# Servorino_FT230X_brick_logic.net
KiCad netlist of a schematic drawn in EAGLE
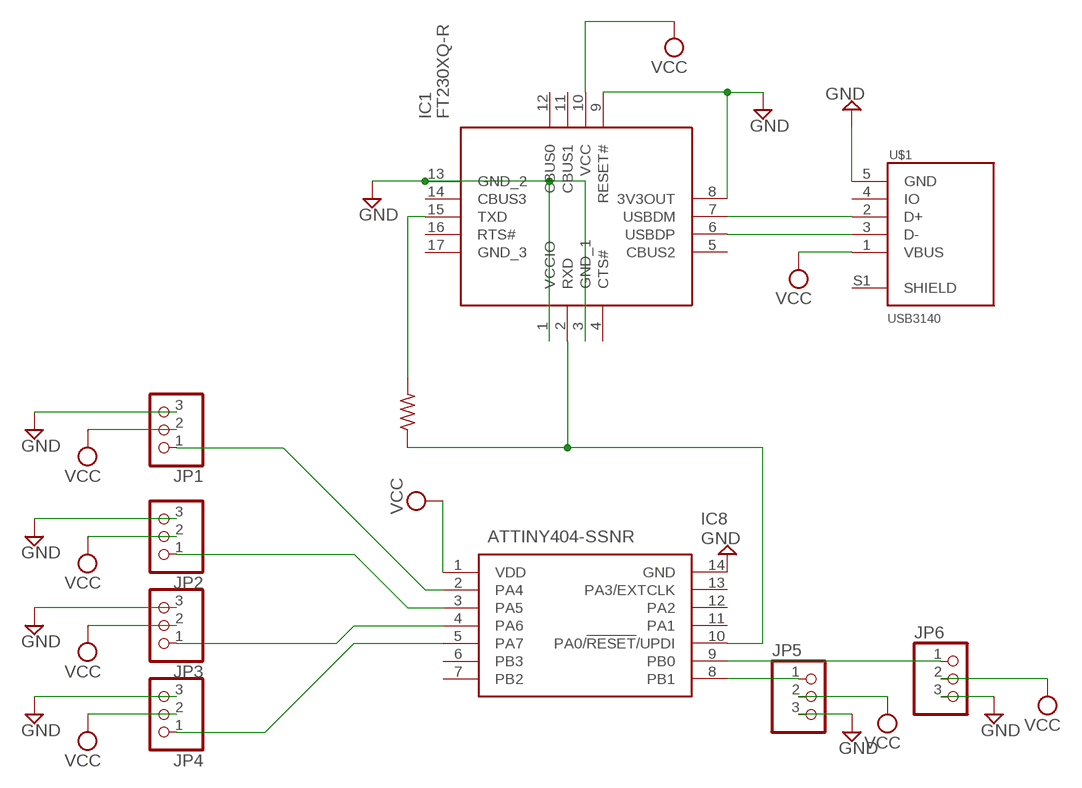
[diagram p0: schematic, sheet 1]

(export (version "E")
  (design (tool "Eeschema 10.0.6"))
  (components
    (comp (ref "IC1")
      (value "FT230XQ-R")
      (footprint "eagle-import:QFN65P400X400X80-17N")
      (fields (field (name "MOUSER_PART_NUMBER") "895-FT230XQ-R"))
      (libsource (lib "eagle-import") (part "FT230XQ-R"))
    )
    (comp (ref "IC8")
      (value "ATTINY404-SSNR")
      (footprint "eagle-import:SOIC127P600X175-14N")
      (fields (field (name "MOUSER_PART_NUMBER") "556-ATTINY404-SSNR"))
      (libsource (lib "eagle-import") (part "ATTINY404-SSNR"))
    )
    (comp (ref "JP1")
      (value "PINHD-1X3")
      (footprint "eagle-import:1X03")
      (libsource (lib "eagle-import") (part "PINHD-1X3"))
    )
    (comp (ref "JP2")
      (value "PINHD-1X3")
      (footprint "eagle-import:1X03")
      (libsource (lib "eagle-import") (part "PINHD-1X3"))
    )
    (comp (ref "JP3")
      (value "PINHD-1X3")
      (footprint "eagle-import:1X03")
      (libsource (lib "eagle-import") (part "PINHD-1X3"))
    )
    (comp (ref "JP4")
      (value "PINHD-1X3")
      (footprint "eagle-import:1X03")
      (libsource (lib "eagle-import") (part "PINHD-1X3"))
    )
    (comp (ref "JP5")
      (value "PINHD-1X3")
      (footprint "eagle-import:1X03")
      (libsource (lib "eagle-import") (part "PINHD-1X3"))
    )
    (comp (ref "JP6")
      (value "PINHD-1X3")
      (footprint "eagle-import:1X03")
      (libsource (lib "eagle-import") (part "PINHD-1X3"))
    )
    (comp (ref "R6")
      (value "470")
      (footprint "eagle-import:R0805")
      (libsource (lib "eagle-import") (part "R-US_R0805"))
    )
    (comp (ref "U$1")
      (value "USB3140")
      (footprint "eagle-import:USB3140-30-0170-0-C")
      (libsource (lib "eagle-import") (part "USB3140"))
    )
  )
  (nets
    (net (code "1") (name "GND") (class "Default")
      (node (ref "IC1") (pin "1") (pinfunction "VCCIO_1") (pintype "bidirectional"))
      (node (ref "IC1") (pin "13") (pinfunction "GND_2_13") (pintype "bidirectional"))
      (node (ref "IC1") (pin "3") (pinfunction "GND_1_3") (pintype "bidirectional"))
      (node (ref "IC1") (pin "8") (pinfunction "3V3OUT_8") (pintype "bidirectional"))
      (node (ref "IC1") (pin "9") (pinfunction "RESET#_9") (pintype "bidirectional"))
      (node (ref "IC8") (pin "14") (pinfunction "GND_14") (pintype "bidirectional"))
      (node (ref "JP1") (pin "3") (pinfunction "3_3") (pintype "passive"))
      (node (ref "JP2") (pin "3") (pinfunction "3_3") (pintype "passive"))
      (node (ref "JP3") (pin "3") (pinfunction "3_3") (pintype "passive"))
      (node (ref "JP4") (pin "3") (pinfunction "3_3") (pintype "passive"))
      (node (ref "JP5") (pin "3") (pinfunction "3_3") (pintype "passive"))
      (node (ref "JP6") (pin "3") (pinfunction "3_3") (pintype "passive"))
      (node (ref "U$1") (pin "5") (pinfunction "GND_5") (pintype "passive"))
    )
    (net (code "2") (name "Net-(IC1-RXD)") (class "Default")
      (node (ref "IC1") (pin "2") (pinfunction "RXD_2") (pintype "bidirectional"))
      (node (ref "IC8") (pin "10") (pinfunction "PA0/~{RESET}/UPDI_10") (pintype "bidirectional"))
      (node (ref "R6") (pin "1") (pinfunction "1_1") (pintype "passive"))
    )
    (net (code "3") (name "Net-(IC1-TXD)") (class "Default")
      (node (ref "IC1") (pin "15") (pinfunction "TXD_15") (pintype "bidirectional"))
      (node (ref "R6") (pin "2") (pinfunction "2_2") (pintype "passive"))
    )
    (net (code "4") (name "Net-(IC1-USBDM)") (class "Default")
      (node (ref "IC1") (pin "7") (pinfunction "USBDM_7") (pintype "bidirectional"))
      (node (ref "U$1") (pin "2") (pinfunction "D+_2") (pintype "passive"))
    )
    (net (code "5") (name "Net-(IC1-USBDP)") (class "Default")
      (node (ref "IC1") (pin "6") (pinfunction "USBDP_6") (pintype "bidirectional"))
      (node (ref "U$1") (pin "3") (pinfunction "D-_3") (pintype "passive"))
    )
    (net (code "6") (name "Net-(IC8-PA4)") (class "Default")
      (node (ref "IC8") (pin "2") (pinfunction "PA4_2") (pintype "bidirectional"))
      (node (ref "JP1") (pin "1") (pinfunction "1_1") (pintype "passive"))
    )
    (net (code "7") (name "Net-(IC8-PA5)") (class "Default")
      (node (ref "IC8") (pin "3") (pinfunction "PA5_3") (pintype "bidirectional"))
      (node (ref "JP2") (pin "1") (pinfunction "1_1") (pintype "passive"))
    )
    (net (code "8") (name "Net-(IC8-PA6)") (class "Default")
      (node (ref "IC8") (pin "4") (pinfunction "PA6_4") (pintype "bidirectional"))
      (node (ref "JP3") (pin "1") (pinfunction "1_1") (pintype "passive"))
    )
    (net (code "9") (name "Net-(IC8-PA7)") (class "Default")
      (node (ref "IC8") (pin "5") (pinfunction "PA7_5") (pintype "bidirectional"))
      (node (ref "JP4") (pin "1") (pinfunction "1_1") (pintype "passive"))
    )
    (net (code "10") (name "Net-(IC8-PB0)") (class "Default")
      (node (ref "IC8") (pin "9") (pinfunction "PB0_9") (pintype "bidirectional"))
      (node (ref "JP6") (pin "1") (pinfunction "1_1") (pintype "passive"))
    )
    (net (code "11") (name "Net-(IC8-PB1)") (class "Default")
      (node (ref "IC8") (pin "8") (pinfunction "PB1_8") (pintype "bidirectional"))
      (node (ref "JP5") (pin "1") (pinfunction "1_1") (pintype "passive"))
    )
    (net (code "12") (name "VCC") (class "Default")
      (node (ref "IC1") (pin "10") (pinfunction "VCC_10") (pintype "bidirectional"))
      (node (ref "IC8") (pin "1") (pinfunction "VDD_1") (pintype "bidirectional"))
      (node (ref "JP1") (pin "2") (pinfunction "2_2") (pintype "passive"))
      (node (ref "JP2") (pin "2") (pinfunction "2_2") (pintype "passive"))
      (node (ref "JP3") (pin "2") (pinfunction "2_2") (pintype "passive"))
      (node (ref "JP4") (pin "2") (pinfunction "2_2") (pintype "passive"))
      (node (ref "JP5") (pin "2") (pinfunction "2_2") (pintype "passive"))
      (node (ref "JP6") (pin "2") (pinfunction "2_2") (pintype "passive"))
      (node (ref "U$1") (pin "1") (pinfunction "VBUS_1") (pintype "passive"))
    )
    (net (code "13") (name "unconnected-(IC1-CBUS0-Pad12)") (class "Default")
      (node (ref "IC1") (pin "12") (pinfunction "CBUS0_12") (pintype "bidirectional"))
    )
    (net (code "14") (name "unconnected-(IC1-CBUS1-Pad11)") (class "Default")
      (node (ref "IC1") (pin "11") (pinfunction "CBUS1_11") (pintype "bidirectional"))
    )
    (net (code "15") (name "unconnected-(IC1-CBUS2-Pad5)") (class "Default")
      (node (ref "IC1") (pin "5") (pinfunction "CBUS2_5") (pintype "bidirectional"))
    )
    (net (code "16") (name "unconnected-(IC1-CBUS3-Pad14)") (class "Default")
      (node (ref "IC1") (pin "14") (pinfunction "CBUS3_14") (pintype "bidirectional"))
    )
    (net (code "17") (name "unconnected-(IC1-CTS#-Pad4)") (class "Default")
      (node (ref "IC1") (pin "4") (pinfunction "CTS#_4") (pintype "bidirectional"))
    )
    (net (code "18") (name "unconnected-(IC1-GND_3-Pad17)") (class "Default")
      (node (ref "IC1") (pin "17") (pinfunction "GND_3_17") (pintype "bidirectional"))
    )
    (net (code "19") (name "unconnected-(IC1-RTS#-Pad16)") (class "Default")
      (node (ref "IC1") (pin "16") (pinfunction "RTS#_16") (pintype "bidirectional"))
    )
    (net (code "20") (name "unconnected-(IC8-PA1-Pad11)") (class "Default")
      (node (ref "IC8") (pin "11") (pinfunction "PA1_11") (pintype "bidirectional"))
    )
    (net (code "21") (name "unconnected-(IC8-PA2-Pad12)") (class "Default")
      (node (ref "IC8") (pin "12") (pinfunction "PA2_12") (pintype "bidirectional"))
    )
    (net (code "22") (name "unconnected-(IC8-PA3{slash}EXTCLK-Pad13)") (class "Default")
      (node (ref "IC8") (pin "13") (pinfunction "PA3/EXTCLK_13") (pintype "bidirectional"))
    )
    (net (code "23") (name "unconnected-(IC8-PB2-Pad7)") (class "Default")
      (node (ref "IC8") (pin "7") (pinfunction "PB2_7") (pintype "bidirectional"))
    )
    (net (code "24") (name "unconnected-(IC8-PB3-Pad6)") (class "Default")
      (node (ref "IC8") (pin "6") (pinfunction "PB3_6") (pintype "bidirectional"))
    )
    (net (code "25") (name "unconnected-(U$1-IO-Pad4)") (class "Default")
      (node (ref "U$1") (pin "4") (pinfunction "IO_4") (pintype "passive"))
    )
    (net (code "26") (name "unconnected-(U$1-SHIELD-PadS1)") (class "Default")
      (node (ref "U$1") (pin "S1") (pinfunction "SHIELD_S1") (pintype "passive"))
    )
  )
)
